# module-pre-amp.net
KiCad netlist of a schematic drawn in EAGLE
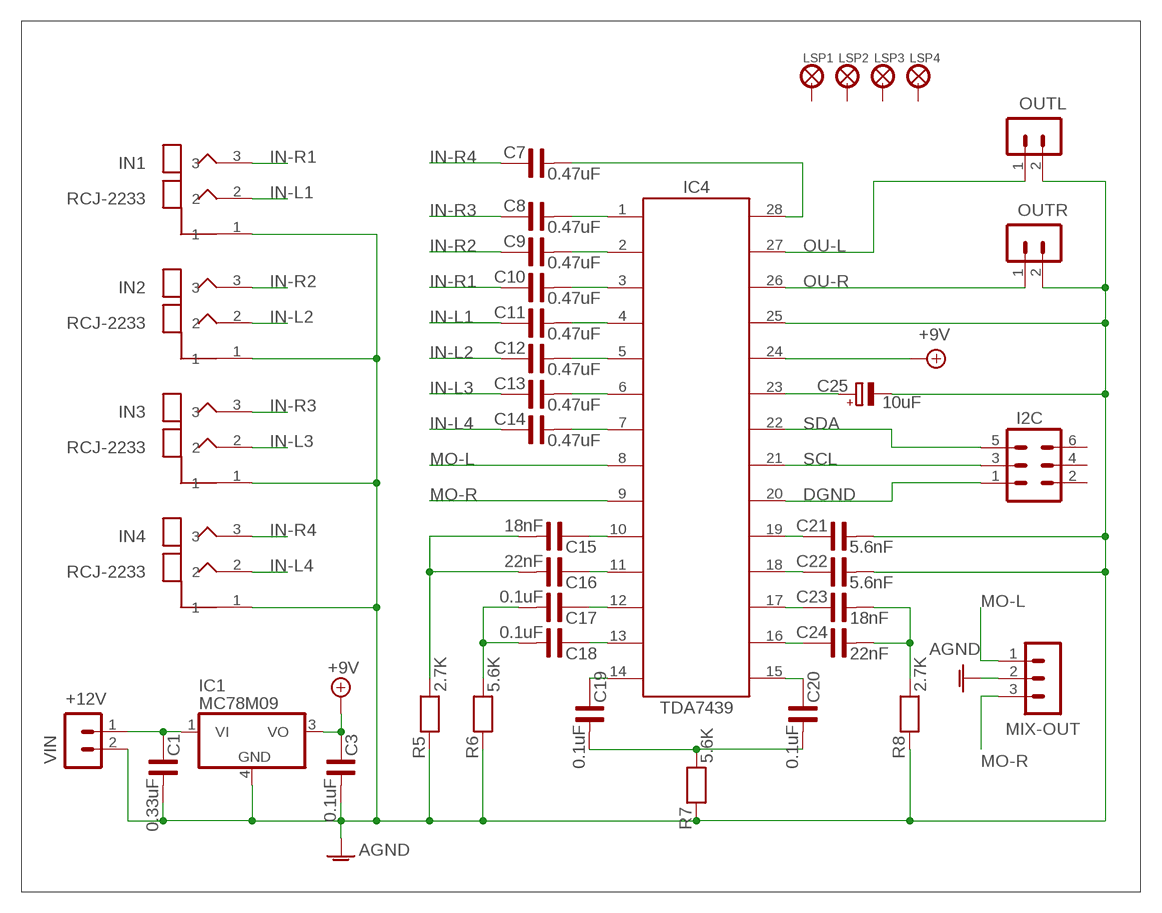
[diagram p0: schematic, sheet 1]

(export (version "E")
  (design (tool "Eeschema 10.0.6"))
  (components
    (comp (ref "C1")
      (value "0.33uF")
      (footprint "eagle-import:C1206")
      (libsource (lib "eagle-import") (part "C-US1206"))
    )
    (comp (ref "C3")
      (value "0.1uF")
      (footprint "eagle-import:C1206")
      (libsource (lib "eagle-import") (part "C-US1206"))
    )
    (comp (ref "C7")
      (value "0.47uF")
      (footprint "eagle-import:C0805")
      (libsource (lib "eagle-import") (part "C-US0805"))
    )
    (comp (ref "C8")
      (value "0.47uF")
      (footprint "eagle-import:C0805")
      (libsource (lib "eagle-import") (part "C-US0805"))
    )
    (comp (ref "C9")
      (value "0.47uF")
      (footprint "eagle-import:C0805")
      (libsource (lib "eagle-import") (part "C-US0805"))
    )
    (comp (ref "C10")
      (value "0.47uF")
      (footprint "eagle-import:C0805")
      (libsource (lib "eagle-import") (part "C-US0805"))
    )
    (comp (ref "C11")
      (value "0.47uF")
      (footprint "eagle-import:C0805")
      (libsource (lib "eagle-import") (part "C-US0805"))
    )
    (comp (ref "C12")
      (value "0.47uF")
      (footprint "eagle-import:C0805")
      (libsource (lib "eagle-import") (part "C-US0805"))
    )
    (comp (ref "C13")
      (value "0.47uF")
      (footprint "eagle-import:C0805")
      (libsource (lib "eagle-import") (part "C-US0805"))
    )
    (comp (ref "C14")
      (value "0.47uF")
      (footprint "eagle-import:C0805")
      (libsource (lib "eagle-import") (part "C-US0805"))
    )
    (comp (ref "C15")
      (value "18nF")
      (footprint "eagle-import:C0805")
      (libsource (lib "eagle-import") (part "C-US0805"))
    )
    (comp (ref "C16")
      (value "22nF")
      (footprint "eagle-import:C0805")
      (libsource (lib "eagle-import") (part "C-US0805"))
    )
    (comp (ref "C17")
      (value "0.1uF")
      (footprint "eagle-import:C0805")
      (libsource (lib "eagle-import") (part "C-US0805"))
    )
    (comp (ref "C18")
      (value "0.1uF")
      (footprint "eagle-import:C0805")
      (libsource (lib "eagle-import") (part "C-US0805"))
    )
    (comp (ref "C19")
      (value "0.1uF")
      (footprint "eagle-import:C0805")
      (libsource (lib "eagle-import") (part "C-US0805"))
    )
    (comp (ref "C20")
      (value "0.1uF")
      (footprint "eagle-import:C0805")
      (libsource (lib "eagle-import") (part "C-US0805"))
    )
    (comp (ref "C21")
      (value "5.6nF")
      (footprint "eagle-import:C0805")
      (libsource (lib "eagle-import") (part "C-US0805"))
    )
    (comp (ref "C22")
      (value "5.6nF")
      (footprint "eagle-import:C0805")
      (libsource (lib "eagle-import") (part "C-US0805"))
    )
    (comp (ref "C23")
      (value "18nF")
      (footprint "eagle-import:C0805")
      (libsource (lib "eagle-import") (part "C-US0805"))
    )
    (comp (ref "C24")
      (value "22nF")
      (footprint "eagle-import:C0805")
      (libsource (lib "eagle-import") (part "C-US0805"))
    )
    (comp (ref "C25")
      (value "10uF")
      (footprint "eagle-import:E2,5-7")
      (libsource (lib "eagle-import") (part "CPOL-EUE2.5-7"))
    )
    (comp (ref "I2C")
      (value "MA03-2")
      (footprint "eagle-import:MA03-2")
      (libsource (lib "eagle-import") (part "MA03-2"))
    )
    (comp (ref "IC1")
      (value "MC78M09")
      (footprint "eagle-import:DPACK_3")
      (libsource (lib "eagle-import") (part "MC78M09CDTG"))
    )
    (comp (ref "IC4")
      (value "TDA7439")
      (footprint "eagle-import:SO28W")
      (libsource (lib "eagle-import") (part "TDA7439"))
    )
    (comp (ref "IN1")
      (value "RCJ-2233")
      (footprint "eagle-import:RCJ-2233")
      (libsource (lib "eagle-import") (part "RCJ-2233"))
    )
    (comp (ref "IN2")
      (value "RCJ-2233")
      (footprint "eagle-import:RCJ-2233")
      (libsource (lib "eagle-import") (part "RCJ-2233"))
    )
    (comp (ref "IN3")
      (value "RCJ-2233")
      (footprint "eagle-import:RCJ-2233")
      (libsource (lib "eagle-import") (part "RCJ-2233"))
    )
    (comp (ref "IN4")
      (value "RCJ-2233")
      (footprint "eagle-import:RCJ-2233")
      (libsource (lib "eagle-import") (part "RCJ-2233"))
    )
    (comp (ref "LSP1")
      (value "LSP27")
      (footprint "eagle-import:LSP27")
      (libsource (lib "eagle-import") (part "LSP27"))
    )
    (comp (ref "LSP2")
      (value "LSP27")
      (footprint "eagle-import:LSP27")
      (libsource (lib "eagle-import") (part "LSP27"))
    )
    (comp (ref "LSP3")
      (value "LSP27")
      (footprint "eagle-import:LSP27")
      (libsource (lib "eagle-import") (part "LSP27"))
    )
    (comp (ref "LSP4")
      (value "LSP27")
      (footprint "eagle-import:LSP27")
      (libsource (lib "eagle-import") (part "LSP27"))
    )
    (comp (ref "MIX-OUT")
      (value "MA03-1PL")
      (footprint "eagle-import:MA03-1")
      (libsource (lib "eagle-import") (part "MA03-1PL"))
    )
    (comp (ref "OUTL")
      (value "MA02-1GREEN")
      (footprint "eagle-import:MA02-1-GREEN")
      (libsource (lib "eagle-import") (part "MA02-1GREEN"))
    )
    (comp (ref "OUTR")
      (value "MA02-1GREEN")
      (footprint "eagle-import:MA02-1-GREEN")
      (libsource (lib "eagle-import") (part "MA02-1GREEN"))
    )
    (comp (ref "R5")
      (value "2.7K")
      (footprint "eagle-import:R0805")
      (libsource (lib "eagle-import") (part "R-US0805"))
    )
    (comp (ref "R6")
      (value "5.6K")
      (footprint "eagle-import:R0805")
      (libsource (lib "eagle-import") (part "R-US0805"))
    )
    (comp (ref "R7")
      (value "5.6K")
      (footprint "eagle-import:R0805")
      (libsource (lib "eagle-import") (part "R-US0805"))
    )
    (comp (ref "R8")
      (value "2.7K")
      (footprint "eagle-import:R0805")
      (libsource (lib "eagle-import") (part "R-US0805"))
    )
    (comp (ref "VIN")
      (value "MA02-1GREEN")
      (footprint "eagle-import:MA02-1-GREEN")
      (libsource (lib "eagle-import") (part "MA02-1GREEN"))
    )
  )
  (nets
    (net (code "1") (name "+9V") (class "Default")
      (node (ref "C3") (pin "1") (pinfunction "1_1") (pintype "passive"))
      (node (ref "IC1") (pin "3") (pinfunction "VO_3") (pintype "passive"))
      (node (ref "IC4") (pin "24") (pinfunction "P$24_24") (pintype "bidirectional"))
    )
    (net (code "2") (name "/+12V") (class "Default")
      (node (ref "C1") (pin "1") (pinfunction "1_1") (pintype "passive"))
      (node (ref "IC1") (pin "1") (pinfunction "VI_1") (pintype "input"))
      (node (ref "VIN") (pin "1") (pinfunction "1_1") (pintype "passive"))
    )
    (net (code "3") (name "/DGND") (class "Default")
      (node (ref "I2C") (pin "1") (pinfunction "1_1") (pintype "passive"))
      (node (ref "IC4") (pin "20") (pinfunction "P$20_20") (pintype "bidirectional"))
    )
    (net (code "4") (name "/IN-L1") (class "Default")
      (node (ref "C11") (pin "1") (pinfunction "1_1") (pintype "passive"))
      (node (ref "IN1") (pin "2") (pinfunction "2_2") (pintype "bidirectional"))
    )
    (net (code "5") (name "/IN-L2") (class "Default")
      (node (ref "C12") (pin "1") (pinfunction "1_1") (pintype "passive"))
      (node (ref "IN2") (pin "2") (pinfunction "2_2") (pintype "bidirectional"))
    )
    (net (code "6") (name "/IN-L3") (class "Default")
      (node (ref "C13") (pin "1") (pinfunction "1_1") (pintype "passive"))
      (node (ref "IN3") (pin "2") (pinfunction "2_2") (pintype "bidirectional"))
    )
    (net (code "7") (name "/IN-L4") (class "Default")
      (node (ref "C14") (pin "1") (pinfunction "1_1") (pintype "passive"))
      (node (ref "IN4") (pin "2") (pinfunction "2_2") (pintype "bidirectional"))
    )
    (net (code "8") (name "/IN-R1") (class "Default")
      (node (ref "C10") (pin "1") (pinfunction "1_1") (pintype "passive"))
      (node (ref "IN1") (pin "3") (pinfunction "3_3") (pintype "bidirectional"))
    )
    (net (code "9") (name "/IN-R2") (class "Default")
      (node (ref "C9") (pin "1") (pinfunction "1_1") (pintype "passive"))
      (node (ref "IN2") (pin "3") (pinfunction "3_3") (pintype "bidirectional"))
    )
    (net (code "10") (name "/IN-R3") (class "Default")
      (node (ref "C8") (pin "1") (pinfunction "1_1") (pintype "passive"))
      (node (ref "IN3") (pin "3") (pinfunction "3_3") (pintype "bidirectional"))
    )
    (net (code "11") (name "/IN-R4") (class "Default")
      (node (ref "C7") (pin "1") (pinfunction "1_1") (pintype "passive"))
      (node (ref "IN4") (pin "3") (pinfunction "3_3") (pintype "bidirectional"))
    )
    (net (code "12") (name "/MO-L") (class "Default")
      (node (ref "IC4") (pin "8") (pinfunction "P$8_8") (pintype "bidirectional"))
      (node (ref "MIX-OUT") (pin "1") (pinfunction "1_1") (pintype "passive"))
    )
    (net (code "13") (name "/MO-R") (class "Default")
      (node (ref "IC4") (pin "9") (pinfunction "P$9_9") (pintype "bidirectional"))
      (node (ref "MIX-OUT") (pin "3") (pinfunction "3_3") (pintype "passive"))
    )
    (net (code "14") (name "/OU-L") (class "Default")
      (node (ref "IC4") (pin "27") (pinfunction "P$27_27") (pintype "bidirectional"))
      (node (ref "OUTL") (pin "1") (pinfunction "1_1") (pintype "passive"))
    )
    (net (code "15") (name "/OU-R") (class "Default")
      (node (ref "IC4") (pin "26") (pinfunction "P$26_26") (pintype "bidirectional"))
      (node (ref "OUTR") (pin "1") (pinfunction "1_1") (pintype "passive"))
    )
    (net (code "16") (name "/SCL") (class "Default")
      (node (ref "I2C") (pin "3") (pinfunction "3_3") (pintype "passive"))
      (node (ref "IC4") (pin "21") (pinfunction "P$21_21") (pintype "bidirectional"))
    )
    (net (code "17") (name "/SDA") (class "Default")
      (node (ref "I2C") (pin "5") (pinfunction "5_5") (pintype "passive"))
      (node (ref "IC4") (pin "22") (pinfunction "P$22_22") (pintype "bidirectional"))
    )
    (net (code "18") (name "AGND") (class "Default")
      (node (ref "C1") (pin "2") (pinfunction "2_2") (pintype "passive"))
      (node (ref "C21") (pin "2") (pinfunction "2_2") (pintype "passive"))
      (node (ref "C22") (pin "2") (pinfunction "2_2") (pintype "passive"))
      (node (ref "C25") (pin "-") (pinfunction "-_-") (pintype "passive"))
      (node (ref "C3") (pin "2") (pinfunction "2_2") (pintype "passive"))
      (node (ref "IC1") (pin "4") (pinfunction "GND_4") (pintype "passive"))
      (node (ref "IC4") (pin "25") (pinfunction "P$25_25") (pintype "bidirectional"))
      (node (ref "IN1") (pin "1") (pinfunction "1_1") (pintype "bidirectional"))
      (node (ref "IN2") (pin "1") (pinfunction "1_1") (pintype "bidirectional"))
      (node (ref "IN3") (pin "1") (pinfunction "1_1") (pintype "bidirectional"))
      (node (ref "IN4") (pin "1") (pinfunction "1_1") (pintype "bidirectional"))
      (node (ref "MIX-OUT") (pin "2") (pinfunction "2_2") (pintype "passive"))
      (node (ref "OUTL") (pin "2") (pinfunction "2_2") (pintype "passive"))
      (node (ref "OUTR") (pin "2") (pinfunction "2_2") (pintype "passive"))
      (node (ref "R5") (pin "1") (pinfunction "1_1") (pintype "passive"))
      (node (ref "R6") (pin "1") (pinfunction "1_1") (pintype "passive"))
      (node (ref "R7") (pin "1") (pinfunction "1_1") (pintype "passive"))
      (node (ref "R8") (pin "1") (pinfunction "1_1") (pintype "passive"))
      (node (ref "VIN") (pin "2") (pinfunction "2_2") (pintype "passive"))
    )
    (net (code "19") (name "Net-(C15-Pad2)") (class "Default")
      (node (ref "C15") (pin "2") (pinfunction "2_2") (pintype "passive"))
      (node (ref "C16") (pin "2") (pinfunction "2_2") (pintype "passive"))
      (node (ref "R5") (pin "2") (pinfunction "2_2") (pintype "passive"))
    )
    (net (code "20") (name "Net-(C17-Pad2)") (class "Default")
      (node (ref "C17") (pin "2") (pinfunction "2_2") (pintype "passive"))
      (node (ref "C18") (pin "2") (pinfunction "2_2") (pintype "passive"))
      (node (ref "R6") (pin "2") (pinfunction "2_2") (pintype "passive"))
    )
    (net (code "21") (name "Net-(C19-Pad2)") (class "Default")
      (node (ref "C19") (pin "2") (pinfunction "2_2") (pintype "passive"))
      (node (ref "C20") (pin "2") (pinfunction "2_2") (pintype "passive"))
      (node (ref "R7") (pin "2") (pinfunction "2_2") (pintype "passive"))
    )
    (net (code "22") (name "Net-(C23-Pad2)") (class "Default")
      (node (ref "C23") (pin "2") (pinfunction "2_2") (pintype "passive"))
      (node (ref "C24") (pin "2") (pinfunction "2_2") (pintype "passive"))
      (node (ref "R8") (pin "2") (pinfunction "2_2") (pintype "passive"))
    )
    (net (code "23") (name "Net-(IC4-P$1)") (class "Default")
      (node (ref "C8") (pin "2") (pinfunction "2_2") (pintype "passive"))
      (node (ref "IC4") (pin "1") (pinfunction "P$1_1") (pintype "bidirectional"))
    )
    (net (code "24") (name "Net-(IC4-P$2)") (class "Default")
      (node (ref "C9") (pin "2") (pinfunction "2_2") (pintype "passive"))
      (node (ref "IC4") (pin "2") (pinfunction "P$2_2") (pintype "bidirectional"))
    )
    (net (code "25") (name "Net-(IC4-P$3)") (class "Default")
      (node (ref "C10") (pin "2") (pinfunction "2_2") (pintype "passive"))
      (node (ref "IC4") (pin "3") (pinfunction "P$3_3") (pintype "bidirectional"))
    )
    (net (code "26") (name "Net-(IC4-P$4)") (class "Default")
      (node (ref "C11") (pin "2") (pinfunction "2_2") (pintype "passive"))
      (node (ref "IC4") (pin "4") (pinfunction "P$4_4") (pintype "bidirectional"))
    )
    (net (code "27") (name "Net-(IC4-P$5)") (class "Default")
      (node (ref "C12") (pin "2") (pinfunction "2_2") (pintype "passive"))
      (node (ref "IC4") (pin "5") (pinfunction "P$5_5") (pintype "bidirectional"))
    )
    (net (code "28") (name "Net-(IC4-P$6)") (class "Default")
      (node (ref "C13") (pin "2") (pinfunction "2_2") (pintype "passive"))
      (node (ref "IC4") (pin "6") (pinfunction "P$6_6") (pintype "bidirectional"))
    )
    (net (code "29") (name "Net-(IC4-P$7)") (class "Default")
      (node (ref "C14") (pin "2") (pinfunction "2_2") (pintype "passive"))
      (node (ref "IC4") (pin "7") (pinfunction "P$7_7") (pintype "bidirectional"))
    )
    (net (code "30") (name "Net-(IC4-P$10)") (class "Default")
      (node (ref "C15") (pin "1") (pinfunction "1_1") (pintype "passive"))
      (node (ref "IC4") (pin "10") (pinfunction "P$10_10") (pintype "bidirectional"))
    )
    (net (code "31") (name "Net-(IC4-P$11)") (class "Default")
      (node (ref "C16") (pin "1") (pinfunction "1_1") (pintype "passive"))
      (node (ref "IC4") (pin "11") (pinfunction "P$11_11") (pintype "bidirectional"))
    )
    (net (code "32") (name "Net-(IC4-P$12)") (class "Default")
      (node (ref "C17") (pin "1") (pinfunction "1_1") (pintype "passive"))
      (node (ref "IC4") (pin "12") (pinfunction "P$12_12") (pintype "bidirectional"))
    )
    (net (code "33") (name "Net-(IC4-P$13)") (class "Default")
      (node (ref "C18") (pin "1") (pinfunction "1_1") (pintype "passive"))
      (node (ref "IC4") (pin "13") (pinfunction "P$13_13") (pintype "bidirectional"))
    )
    (net (code "34") (name "Net-(IC4-P$14)") (class "Default")
      (node (ref "C19") (pin "1") (pinfunction "1_1") (pintype "passive"))
      (node (ref "IC4") (pin "14") (pinfunction "P$14_14") (pintype "bidirectional"))
    )
    (net (code "35") (name "Net-(IC4-P$15)") (class "Default")
      (node (ref "C20") (pin "1") (pinfunction "1_1") (pintype "passive"))
      (node (ref "IC4") (pin "15") (pinfunction "P$15_15") (pintype "bidirectional"))
    )
    (net (code "36") (name "Net-(IC4-P$16)") (class "Default")
      (node (ref "C24") (pin "1") (pinfunction "1_1") (pintype "passive"))
      (node (ref "IC4") (pin "16") (pinfunction "P$16_16") (pintype "bidirectional"))
    )
    (net (code "37") (name "Net-(IC4-P$17)") (class "Default")
      (node (ref "C23") (pin "1") (pinfunction "1_1") (pintype "passive"))
      (node (ref "IC4") (pin "17") (pinfunction "P$17_17") (pintype "bidirectional"))
    )
    (net (code "38") (name "Net-(IC4-P$18)") (class "Default")
      (node (ref "C22") (pin "1") (pinfunction "1_1") (pintype "passive"))
      (node (ref "IC4") (pin "18") (pinfunction "P$18_18") (pintype "bidirectional"))
    )
    (net (code "39") (name "Net-(IC4-P$19)") (class "Default")
      (node (ref "C21") (pin "1") (pinfunction "1_1") (pintype "passive"))
      (node (ref "IC4") (pin "19") (pinfunction "P$19_19") (pintype "bidirectional"))
    )
    (net (code "40") (name "Net-(IC4-P$23)") (class "Default")
      (node (ref "C25") (pin "+") (pinfunction "+_+") (pintype "passive"))
      (node (ref "IC4") (pin "23") (pinfunction "P$23_23") (pintype "bidirectional"))
    )
    (net (code "41") (name "Net-(IC4-P$28)") (class "Default")
      (node (ref "C7") (pin "2") (pinfunction "2_2") (pintype "passive"))
      (node (ref "IC4") (pin "28") (pinfunction "P$28_28") (pintype "bidirectional"))
    )
    (net (code "42") (name "unconnected-(I2C-Pad2)") (class "Default")
      (node (ref "I2C") (pin "2") (pinfunction "2_2") (pintype "passive"))
    )
    (net (code "43") (name "unconnected-(I2C-Pad4)") (class "Default")
      (node (ref "I2C") (pin "4") (pinfunction "4_4") (pintype "passive"))
    )
    (net (code "44") (name "unconnected-(I2C-Pad6)") (class "Default")
      (node (ref "I2C") (pin "6") (pinfunction "6_6") (pintype "passive"))
    )
    (net (code "45") (name "unconnected-(LSP1-PadMP)") (class "Default")
      (node (ref "LSP1") (pin "MP") (pinfunction "MP_MP") (pintype "passive"))
    )
    (net (code "46") (name "unconnected-(LSP2-PadMP)") (class "Default")
      (node (ref "LSP2") (pin "MP") (pinfunction "MP_MP") (pintype "passive"))
    )
    (net (code "47") (name "unconnected-(LSP3-PadMP)") (class "Default")
      (node (ref "LSP3") (pin "MP") (pinfunction "MP_MP") (pintype "passive"))
    )
    (net (code "48") (name "unconnected-(LSP4-PadMP)") (class "Default")
      (node (ref "LSP4") (pin "MP") (pinfunction "MP_MP") (pintype "passive"))
    )
  )
)
